# Supplemental_Power_Switch_System.net
KiCad netlist of a schematic drawn in EAGLE
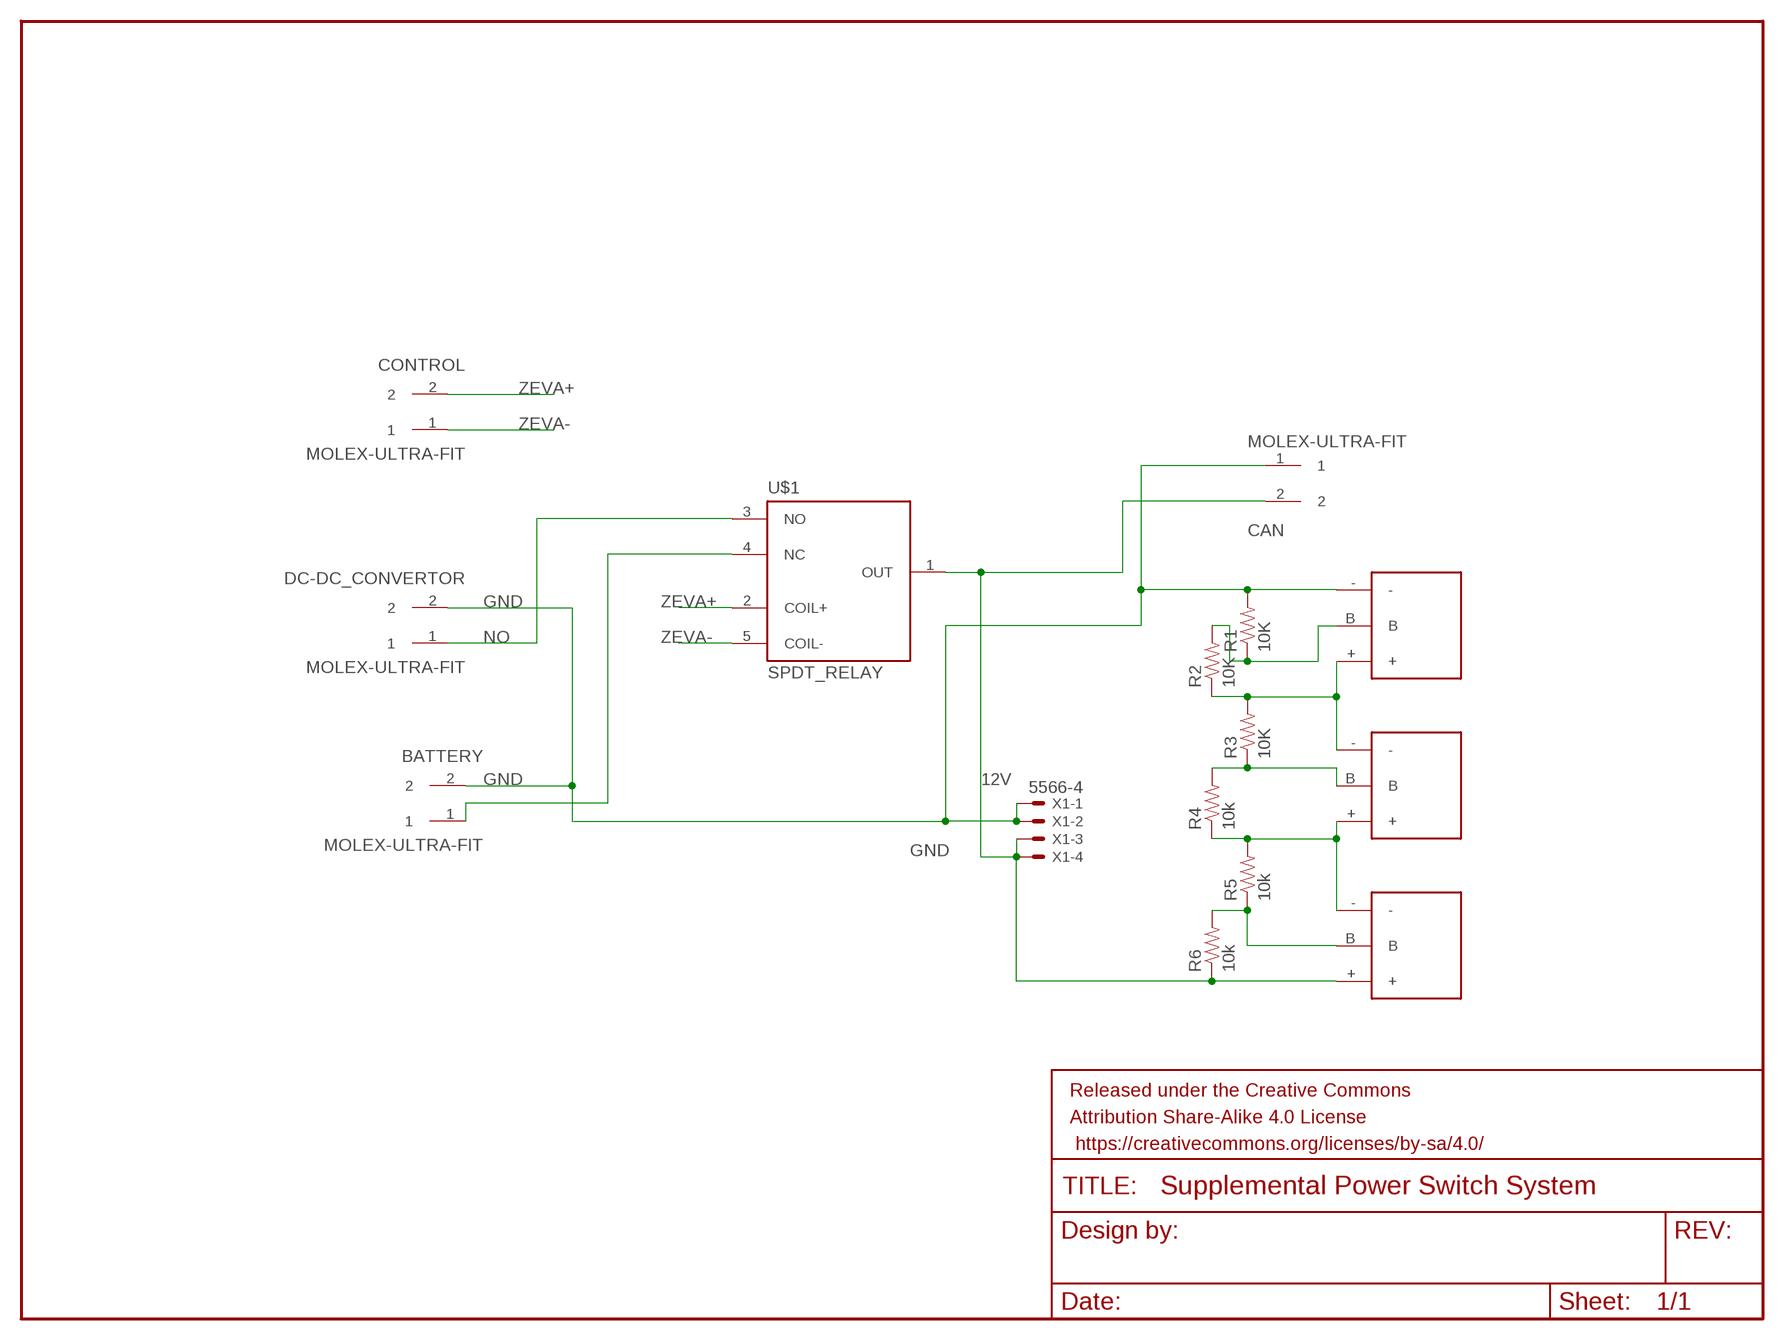
[diagram p0: schematic, sheet 1]

(export (version "E")
  (design (tool "Eeschema 10.0.6"))
  (components
    (comp (ref "BATTERY")
      (value "MOLEX-ULTRA-FIT")
      (footprint "eagle-import:MOLEX-172287")
      (libsource (lib "eagle-import") (part "MOLEX-ULTRA-FIT"))
    )
    (comp (ref "C1")
      (value "SUPER-CAPACITOR")
      (footprint "eagle-import:DMF")
      (libsource (lib "eagle-import") (part "SUPER-CAPACITOR"))
    )
    (comp (ref "C2")
      (value "SUPER-CAPACITOR")
      (footprint "eagle-import:DMF")
      (libsource (lib "eagle-import") (part "SUPER-CAPACITOR"))
    )
    (comp (ref "C3")
      (value "SUPER-CAPACITOR")
      (footprint "eagle-import:DMF")
      (libsource (lib "eagle-import") (part "SUPER-CAPACITOR"))
    )
    (comp (ref "CAN")
      (value "MOLEX-ULTRA-FIT")
      (footprint "eagle-import:MOLEX-172287")
      (libsource (lib "eagle-import") (part "MOLEX-ULTRA-FIT"))
    )
    (comp (ref "CONTROL")
      (value "MOLEX-ULTRA-FIT")
      (footprint "eagle-import:MOLEX-172287")
      (libsource (lib "eagle-import") (part "MOLEX-ULTRA-FIT"))
    )
    (comp (ref "DC-DC_CONVERTOR")
      (value "MOLEX-ULTRA-FIT")
      (footprint "eagle-import:MOLEX-172287")
      (libsource (lib "eagle-import") (part "MOLEX-ULTRA-FIT"))
    )
    (comp (ref "FRAME1")
      (value "FRAME-LETTERNO_PACKAGE")
      (footprint "eagle-import:DUMMY")
      (fields (field (name "DESIGNER") "Nobody"))
      (libsource (lib "eagle-import") (part "FRAME-LETTERNO_PACKAGE"))
    )
    (comp (ref "R1")
      (value "10K")
      (footprint "eagle-import:1206")
      (libsource (lib "eagle-import") (part "RESISTOR1206"))
    )
    (comp (ref "R2")
      (value "10K")
      (footprint "eagle-import:1206")
      (libsource (lib "eagle-import") (part "RESISTOR1206"))
    )
    (comp (ref "R3")
      (value "10K")
      (footprint "eagle-import:1206")
      (libsource (lib "eagle-import") (part "RESISTOR1206"))
    )
    (comp (ref "R4")
      (value "10k")
      (footprint "eagle-import:1206")
      (libsource (lib "eagle-import") (part "RESISTOR1206"))
    )
    (comp (ref "R5")
      (value "10k")
      (footprint "eagle-import:1206")
      (libsource (lib "eagle-import") (part "RESISTOR1206"))
    )
    (comp (ref "R6")
      (value "10k")
      (footprint "eagle-import:1206")
      (libsource (lib "eagle-import") (part "RESISTOR1206"))
    )
    (comp (ref "U$1")
      (value "SPDT_RELAY")
      (footprint "eagle-import:G8QN-1C4")
      (libsource (lib "eagle-import") (part "SPDT_RELAY"))
    )
    (comp (ref "X1")
      (value "5566-4")
      (footprint "eagle-import:5566-4")
      (libsource (lib "eagle-import") (part "5566-4"))
    )
  )
  (nets
    (net (code "1") (name "/12V") (class "Default")
      (node (ref "C3") (pin "+") (pinfunction "+_+") (pintype "bidirectional"))
      (node (ref "CAN") (pin "2") (pinfunction "2_2") (pintype "bidirectional"))
      (node (ref "R6") (pin "1") (pinfunction "1_1") (pintype "passive"))
      (node (ref "U$1") (pin "1") (pinfunction "OUT_1") (pintype "output"))
      (node (ref "X1") (pin "3") (pinfunction "S_3") (pintype "passive"))
      (node (ref "X1") (pin "4") (pinfunction "S_4") (pintype "passive"))
    )
    (net (code "2") (name "/GND") (class "Default")
      (node (ref "BATTERY") (pin "2") (pinfunction "2_2") (pintype "bidirectional"))
      (node (ref "C1") (pin "-") (pinfunction "-_-") (pintype "bidirectional"))
      (node (ref "CAN") (pin "1") (pinfunction "1_1") (pintype "bidirectional"))
      (node (ref "DC-DC_CONVERTOR") (pin "2") (pinfunction "2_2") (pintype "bidirectional"))
      (node (ref "R1") (pin "2") (pinfunction "2_2") (pintype "passive"))
      (node (ref "X1") (pin "1") (pinfunction "S_1") (pintype "passive"))
      (node (ref "X1") (pin "2") (pinfunction "S_2") (pintype "passive"))
    )
    (net (code "3") (name "/NO") (class "Default")
      (node (ref "DC-DC_CONVERTOR") (pin "1") (pinfunction "1_1") (pintype "bidirectional"))
      (node (ref "U$1") (pin "3") (pinfunction "NO_3") (pintype "input"))
    )
    (net (code "4") (name "/ZEVA+") (class "Default")
      (node (ref "CONTROL") (pin "2") (pinfunction "2_2") (pintype "bidirectional"))
      (node (ref "U$1") (pin "2") (pinfunction "COIL+_2") (pintype "input"))
    )
    (net (code "5") (name "/ZEVA-") (class "Default")
      (node (ref "CONTROL") (pin "1") (pinfunction "1_1") (pintype "bidirectional"))
      (node (ref "U$1") (pin "5") (pinfunction "COIL-_5") (pintype "input"))
    )
    (net (code "6") (name "Net-(C1-Pad+)") (class "Default")
      (node (ref "C1") (pin "+") (pinfunction "+_+") (pintype "bidirectional"))
      (node (ref "C2") (pin "-") (pinfunction "-_-") (pintype "bidirectional"))
      (node (ref "R2") (pin "1") (pinfunction "1_1") (pintype "passive"))
      (node (ref "R3") (pin "2") (pinfunction "2_2") (pintype "passive"))
    )
    (net (code "7") (name "Net-(C1-PadB)") (class "Default")
      (node (ref "C1") (pin "B") (pinfunction "B_B") (pintype "bidirectional"))
      (node (ref "R1") (pin "1") (pinfunction "1_1") (pintype "passive"))
      (node (ref "R2") (pin "2") (pinfunction "2_2") (pintype "passive"))
    )
    (net (code "8") (name "Net-(C2-Pad+)") (class "Default")
      (node (ref "C2") (pin "+") (pinfunction "+_+") (pintype "bidirectional"))
      (node (ref "C3") (pin "-") (pinfunction "-_-") (pintype "bidirectional"))
      (node (ref "R4") (pin "1") (pinfunction "1_1") (pintype "passive"))
      (node (ref "R5") (pin "2") (pinfunction "2_2") (pintype "passive"))
    )
    (net (code "9") (name "Net-(C2-PadB)") (class "Default")
      (node (ref "C2") (pin "B") (pinfunction "B_B") (pintype "bidirectional"))
      (node (ref "R3") (pin "1") (pinfunction "1_1") (pintype "passive"))
      (node (ref "R4") (pin "2") (pinfunction "2_2") (pintype "passive"))
    )
    (net (code "10") (name "Net-(C3-PadB)") (class "Default")
      (node (ref "C3") (pin "B") (pinfunction "B_B") (pintype "bidirectional"))
      (node (ref "R5") (pin "1") (pinfunction "1_1") (pintype "passive"))
      (node (ref "R6") (pin "2") (pinfunction "2_2") (pintype "passive"))
    )
    (net (code "11") (name "Net-(U$1-NC)") (class "Default")
      (node (ref "BATTERY") (pin "1") (pinfunction "1_1") (pintype "bidirectional"))
      (node (ref "U$1") (pin "4") (pinfunction "NC_4") (pintype "input"))
    )
  )
)
